# Microcontroller.net
KiCad netlist of a schematic drawn in Altium Designer
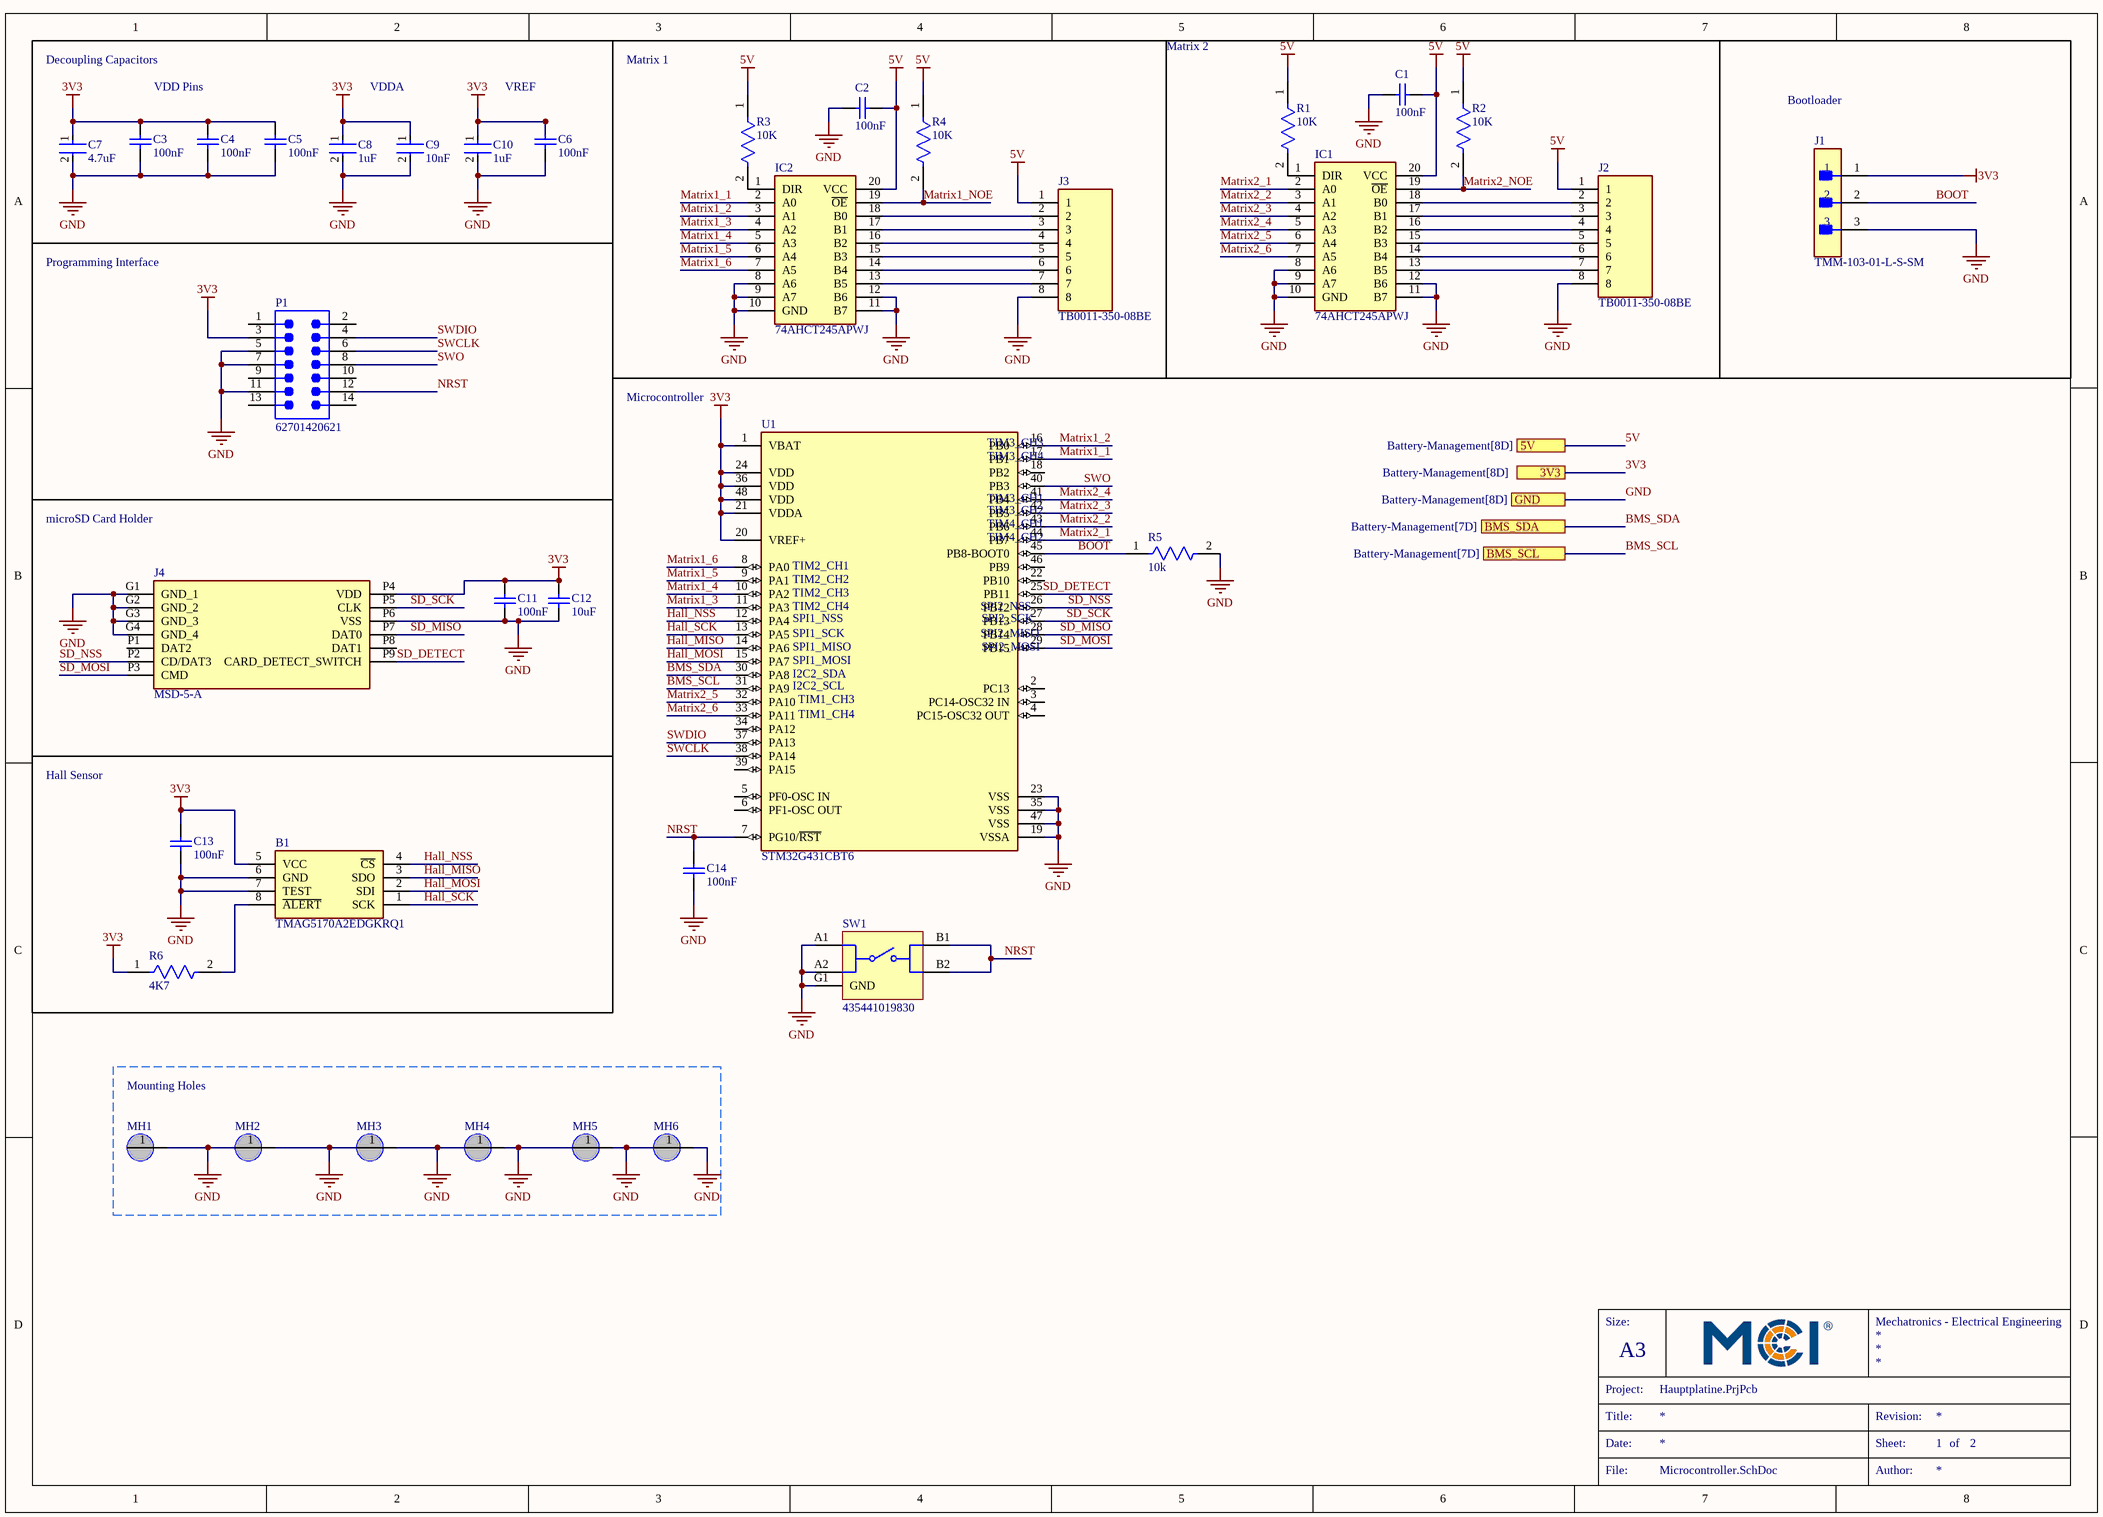
[diagram p0: Microcontroller.SchDoc]

(export (version "E")
  (design (tool "Eeschema 10.0.6"))
  (components
    (comp (ref "B1")
      (value "TMAG5170A2EDGKRQ1")
      (footprint "SOP65P490X110-8N")
      (description "Board Mount Hall Effect/Magnetic Sensors")
      (fields (field (name "MOUSER PART NUMBER") "595-MAG5170A2EDGKRQ1"))
      (libsource (lib "Library") (part "TMAG5170A2EDGKRQ1"))
    )
    (comp (ref "C1")
      (value "100nF")
      (footprint "CAPC2013X145X50LL20T20")
      (fields (field (name "PART NUMBER") "VJ0805Y104JXXPW1BC") (field (name "MANUFACTURER") "Vitramon"))
      (libsource (lib "Altium Content Vault") (part "CAP"))
    )
    (comp (ref "C2")
      (value "100nF")
      (footprint "CAPC2013X145X50LL20T20")
      (fields (field (name "PART NUMBER") "VJ0805Y104JXXPW1BC") (field (name "MANUFACTURER") "Vitramon"))
      (libsource (lib "Altium Content Vault") (part "CAP"))
    )
    (comp (ref "C3")
      (value "100nF")
      (footprint "CAPC2013X145X50LL20T20")
      (fields (field (name "PART NUMBER") "VJ0805Y104JXXPW1BC") (field (name "MANUFACTURER") "Vitramon"))
      (libsource (lib "Altium Content Vault") (part "CAP"))
    )
    (comp (ref "C4")
      (value "100nF")
      (footprint "CAPC2013X145X50LL20T20")
      (fields (field (name "PART NUMBER") "VJ0805Y104JXXPW1BC") (field (name "MANUFACTURER") "Vitramon"))
      (libsource (lib "Altium Content Vault") (part "CAP"))
    )
    (comp (ref "C5")
      (value "100nF")
      (footprint "CAPC2013X145X50LL20T20")
      (fields (field (name "PART NUMBER") "VJ0805Y104JXXPW1BC") (field (name "MANUFACTURER") "Vitramon"))
      (libsource (lib "Altium Content Vault") (part "CAP"))
    )
    (comp (ref "C6")
      (value "100nF")
      (footprint "CAPC2013X145X50LL20T20")
      (fields (field (name "PART NUMBER") "VJ0805Y104JXXPW1BC") (field (name "MANUFACTURER") "Vitramon"))
      (libsource (lib "Altium Content Vault") (part "CAP"))
    )
    (comp (ref "C7")
      (value "4.7uF")
      (footprint "FP-C0805C475K3RACAUTO-MFG")
      (description "CAP CER 0805 4.7UF 25V X7R  10%")
      (libsource (lib "Altium Content Vault") (part "b4654b650e69147ec39a6b967a45e02"))
    )
    (comp (ref "C8")
      (value "1uF")
      (footprint "FP-CC0805-EB-MFG")
      (description "CAP CER 1UF 6.3V X7R 0805")
      (fields (field (name "TOLERANCE") "10%"))
      (libsource (lib "Altium Content Vault") (part "b4654b650e69147ec39a6b967a45e02"))
    )
    (comp (ref "C9")
      (value "10nF")
      (footprint "FP-AC0805-0_85-MFG")
      (description "AC Series 0805 10 nF 100 V ±10% X7R Multilayer Ceramic Capacitor")
      (fields
        (field (name "MANUFACTURER") "Yageo")
        (field (name "OCTOPART") "https://octopart.com/ac0805krx7r0bb103-yageo-75656636")
      )
      (libsource (lib "Altium Content Vault") (part "11868f565c42a9108669ba33697ecf6"))
    )
    (comp (ref "C10")
      (value "1uF")
      (footprint "FP-CC0805-EB-MFG")
      (description "CAP CER 1UF 6.3V X7R 0805")
      (fields (field (name "TOLERANCE") "10%"))
      (libsource (lib "Altium Content Vault") (part "b4654b650e69147ec39a6b967a45e02"))
    )
    (comp (ref "C11")
      (value "100nF")
      (footprint "CAPC2013X145X50LL20T20")
      (fields (field (name "PART NUMBER") "VJ0805Y104JXXPW1BC") (field (name "MANUFACTURER") "Vitramon"))
      (libsource (lib "Altium Content Vault") (part "CAP"))
    )
    (comp (ref "C12")
      (value "10uF")
      (footprint "CAPC2013X140X50ML20T25")
      (fields
        (field (name "MANUFACTURER") "AVX Interconnect / Elco")
        (field (name "PART NUMBER") "0805ZC106KAT2A")
      )
      (libsource (lib "Altium Content Vault") (part "CAP"))
    )
    (comp (ref "C13")
      (value "100nF")
      (footprint "CAPC2013X145X50LL20T20")
      (fields (field (name "PART NUMBER") "VJ0805Y104JXXPW1BC") (field (name "MANUFACTURER") "Vitramon"))
      (libsource (lib "Altium Content Vault") (part "CAP"))
    )
    (comp (ref "C14")
      (value "100nF")
      (footprint "CAPC2013X145X50LL20T20")
      (fields (field (name "PART NUMBER") "VJ0805Y104JXXPW1BC") (field (name "MANUFACTURER") "Vitramon"))
      (libsource (lib "Altium Content Vault") (part "CAP"))
    )
    (comp (ref "IC1")
      (value "74AHCT245APWJ")
      (footprint "Library:SOP65P640X110-20N")
      (description "Integrated Circuit")
      (fields (field (name "MOUSER PART NUMBER") "771-74AHCT245APWJ"))
      (libsource (lib "*") (part "74AHCT245APWJ"))
    )
    (comp (ref "IC2")
      (value "74AHCT245APWJ")
      (footprint "Library:SOP65P640X110-20N")
      (description "Integrated Circuit")
      (fields (field (name "MOUSER PART NUMBER") "771-74AHCT245APWJ"))
      (libsource (lib "*") (part "74AHCT245APWJ"))
    )
    (comp (ref "J1")
      (value "TMM-103-01-L-S-SM")
      (footprint "FP-TMM-103-01-L-S-SM-MFG")
      (description "CONN HEADER SMD 3POS 2MM")
      (libsource (lib "Altium Content Vault") (part "0d3f023dd272f625e17a2be33dea85f"))
    )
    (comp (ref "J2")
      (value "TB0011-350-08BE")
      (footprint "TB0011-350-08BE")
      (description "Connector")
      (libsource (lib "Library") (part "TB0011-350-08BE"))
    )
    (comp (ref "J3")
      (value "TB0011-350-08BE")
      (footprint "TB0011-350-08BE")
      (description "Connector")
      (libsource (lib "Library") (part "TB0011-350-08BE"))
    )
    (comp (ref "J4")
      (value "MSD-5-A")
      (footprint "Library:MSD5A")
      (description "Connector")
      (fields (field (name "MOUSER PART NUMBER") "179-MSD-5-A"))
      (libsource (lib "Library") (part "MSD-5-A"))
    )
    (comp (ref "MH1")
      (value "MountingHole")
      (footprint "MTH")
      (libsource (lib "Motorsteuerung_V5") (part "MountingHole"))
    )
    (comp (ref "MH2")
      (value "MountingHole")
      (footprint "MTH")
      (libsource (lib "Motorsteuerung_V5") (part "MountingHole"))
    )
    (comp (ref "MH3")
      (value "MountingHole")
      (footprint "MTH")
      (libsource (lib "Motorsteuerung_V5") (part "MountingHole"))
    )
    (comp (ref "MH4")
      (value "MountingHole")
      (footprint "MTH")
      (libsource (lib "Motorsteuerung_V5") (part "MountingHole"))
    )
    (comp (ref "MH5")
      (value "MountingHole")
      (footprint "MTH")
      (libsource (lib "Motorsteuerung_V5") (part "MountingHole"))
    )
    (comp (ref "MH6")
      (value "MountingHole")
      (footprint "MTH")
      (libsource (lib "Motorsteuerung_V5") (part "MountingHole"))
    )
    (comp (ref "P1")
      (value "62701420621")
      (footprint "62701420621")
      (description "Conn, Hdr, 14Pos, 2Row, 1.27Mm, Smt Rohs Compliant: Yes")
      (libsource (lib "Altium Content Vault") (part "Header_Male_2R_14P"))
    )
    (comp (ref "R1")
      (value "10K")
      (footprint "FP-AT0805-MFG")
      (description "Thin Film Chip Resistors Automotive Grade 10kΩ 0.5% 50ppm/°C 0805")
      (fields (field (name "TOLERANCE") "0.5%"))
      (libsource (lib "Altium Content Vault") (part "1029c3af85768c4190bb7ad29bc67b5"))
    )
    (comp (ref "R2")
      (value "10K")
      (footprint "FP-AT0805-MFG")
      (description "Thin Film Chip Resistors Automotive Grade 10kΩ 0.5% 50ppm/°C 0805")
      (fields (field (name "TOLERANCE") "0.5%"))
      (libsource (lib "Altium Content Vault") (part "1029c3af85768c4190bb7ad29bc67b5"))
    )
    (comp (ref "R3")
      (value "10K")
      (footprint "FP-AT0805-MFG")
      (description "Thin Film Chip Resistors Automotive Grade 10kΩ 0.5% 50ppm/°C 0805")
      (fields (field (name "TOLERANCE") "0.5%"))
      (libsource (lib "Altium Content Vault") (part "1029c3af85768c4190bb7ad29bc67b5"))
    )
    (comp (ref "R4")
      (value "10K")
      (footprint "FP-AT0805-MFG")
      (description "Thin Film Chip Resistors Automotive Grade 10kΩ 0.5% 50ppm/°C 0805")
      (fields (field (name "TOLERANCE") "0.5%"))
      (libsource (lib "Altium Content Vault") (part "1029c3af85768c4190bb7ad29bc67b5"))
    )
    (comp (ref "R5")
      (value "10k")
      (footprint "FP-AT0805-MFG")
      (description "Thin Film Chip Resistors Automotive Grade 10kΩ 0.5% 50ppm/°C 0805")
      (fields (field (name "TOLERANCE") "0.5%"))
      (libsource (lib "Altium Content Vault") (part "1029c3af85768c4190bb7ad29bc67b5"))
    )
    (comp (ref "R6")
      (value "4K7")
      (footprint "FP-RT0805-MFG")
      (description "RES SMD 47K OHM 1% 1/8W 0805")
      (fields
        (field (name "MANUFACTURER PART NUMBER") "RT0805FRD0747KL")
        (field (name "OCTOPART") "https://octopart.com/rt0805frd0747kl-yageo-71400071")
      )
      (libsource (lib "Altium Content Vault") (part "1029c3af85768c4190bb7ad29bc67b5"))
    )
    (comp (ref "SW1")
      (value "435441019830")
      (footprint "435441019830")
      (description "Tactile Switch, 0.05A, 32Vdc, Smd, 300Gf Rohs Compliant: Yes")
      (libsource (lib "Altium Content Vault") (part "SPST-NO_4P_1GND"))
    )
    (comp (ref "U1")
      (value "STM32G431CBT6")
      (footprint "FP-LQFP48-5B-MFG")
      (description "MAINSTREAM ARM CORTEX-M4+ MCU 17")
      (fields
        (field (name "MANUFACTURER") "STMicroelectronics")
        (field (name "OCTOPART") "https://octopart.com/stm32g431cbt6-stmicroelectronics-98835224")
      )
      (libsource (lib "Altium Content Vault") (part "08b09c1d51ec08ade740842f2b8671b"))
    )
  )
  (nets
    (net (code "1") (name "/BMS_SCL") (class "Default")
      (node (ref "U1") (pin "31") (pinfunction "PA9_31") (pintype "bidirectional"))
    )
    (net (code "2") (name "/BMS_SDA") (class "Default")
      (node (ref "U1") (pin "30") (pinfunction "PA8_30") (pintype "bidirectional"))
    )
    (net (code "3") (name "/BOOT") (class "Default")
      (node (ref "J1") (pin "2") (pinfunction "2_2") (pintype "passive"))
      (node (ref "R5") (pin "1") (pinfunction "1_1") (pintype "passive"))
      (node (ref "U1") (pin "45") (pinfunction "PB8-BOOT0_45") (pintype "bidirectional"))
    )
    (net (code "4") (name "/Hall_MISO") (class "Default")
      (node (ref "B1") (pin "3") (pinfunction "SDO_3") (pintype "passive"))
      (node (ref "U1") (pin "14") (pinfunction "PA6_14") (pintype "bidirectional"))
    )
    (net (code "5") (name "/Hall_MOSI") (class "Default")
      (node (ref "B1") (pin "2") (pinfunction "SDI_2") (pintype "passive"))
      (node (ref "U1") (pin "15") (pinfunction "PA7_15") (pintype "bidirectional"))
    )
    (net (code "6") (name "/Hall_NSS") (class "Default")
      (node (ref "B1") (pin "4") (pinfunction "~{CS}_4") (pintype "passive"))
      (node (ref "U1") (pin "12") (pinfunction "PA4_12") (pintype "bidirectional"))
    )
    (net (code "7") (name "/Hall_SCK") (class "Default")
      (node (ref "B1") (pin "1") (pinfunction "SCK_1") (pintype "passive"))
      (node (ref "U1") (pin "13") (pinfunction "PA5_13") (pintype "bidirectional"))
    )
    (net (code "8") (name "/Matrix1_1") (class "Default")
      (node (ref "IC2") (pin "2") (pinfunction "A0_2") (pintype "passive"))
      (node (ref "U1") (pin "17") (pinfunction "PB1_17") (pintype "bidirectional"))
    )
    (net (code "9") (name "/Matrix1_2") (class "Default")
      (node (ref "IC2") (pin "3") (pinfunction "A1_3") (pintype "passive"))
      (node (ref "U1") (pin "16") (pinfunction "PB0_16") (pintype "bidirectional"))
    )
    (net (code "10") (name "/Matrix1_3") (class "Default")
      (node (ref "IC2") (pin "4") (pinfunction "A2_4") (pintype "passive"))
      (node (ref "U1") (pin "11") (pinfunction "PA3_11") (pintype "bidirectional"))
    )
    (net (code "11") (name "/Matrix1_4") (class "Default")
      (node (ref "IC2") (pin "5") (pinfunction "A3_5") (pintype "passive"))
      (node (ref "U1") (pin "10") (pinfunction "PA2_10") (pintype "bidirectional"))
    )
    (net (code "12") (name "/Matrix1_5") (class "Default")
      (node (ref "IC2") (pin "6") (pinfunction "A4_6") (pintype "passive"))
      (node (ref "U1") (pin "9") (pinfunction "PA1_9") (pintype "bidirectional"))
    )
    (net (code "13") (name "/Matrix1_6") (class "Default")
      (node (ref "IC2") (pin "7") (pinfunction "A5_7") (pintype "passive"))
      (node (ref "U1") (pin "8") (pinfunction "PA0_8") (pintype "bidirectional"))
    )
    (net (code "14") (name "/Matrix1_NOE") (class "Default")
      (node (ref "IC2") (pin "19") (pinfunction "~{OE}_19") (pintype "passive"))
      (node (ref "R4") (pin "2") (pinfunction "2_2") (pintype "passive"))
    )
    (net (code "15") (name "/Matrix2_1") (class "Default")
      (node (ref "IC1") (pin "2") (pinfunction "A0_2") (pintype "passive"))
      (node (ref "U1") (pin "44") (pinfunction "PB7_44") (pintype "bidirectional"))
    )
    (net (code "16") (name "/Matrix2_2") (class "Default")
      (node (ref "IC1") (pin "3") (pinfunction "A1_3") (pintype "passive"))
      (node (ref "U1") (pin "43") (pinfunction "PB6_43") (pintype "bidirectional"))
    )
    (net (code "17") (name "/Matrix2_3") (class "Default")
      (node (ref "IC1") (pin "4") (pinfunction "A2_4") (pintype "passive"))
      (node (ref "U1") (pin "42") (pinfunction "PB5_42") (pintype "bidirectional"))
    )
    (net (code "18") (name "/Matrix2_4") (class "Default")
      (node (ref "IC1") (pin "5") (pinfunction "A3_5") (pintype "passive"))
      (node (ref "U1") (pin "41") (pinfunction "PB4_41") (pintype "bidirectional"))
    )
    (net (code "19") (name "/Matrix2_5") (class "Default")
      (node (ref "IC1") (pin "6") (pinfunction "A4_6") (pintype "passive"))
      (node (ref "U1") (pin "32") (pinfunction "PA10_32") (pintype "bidirectional"))
    )
    (net (code "20") (name "/Matrix2_6") (class "Default")
      (node (ref "IC1") (pin "7") (pinfunction "A5_7") (pintype "passive"))
      (node (ref "U1") (pin "33") (pinfunction "PA11_33") (pintype "bidirectional"))
    )
    (net (code "21") (name "/Matrix2_NOE") (class "Default")
      (node (ref "IC1") (pin "19") (pinfunction "~{OE}_19") (pintype "passive"))
      (node (ref "R2") (pin "2") (pinfunction "2_2") (pintype "passive"))
    )
    (net (code "22") (name "/NRST") (class "Default")
      (node (ref "C14") (pin "2") (pinfunction "2_2") (pintype "passive"))
      (node (ref "P1") (pin "12") (pinfunction "12_12") (pintype "passive"))
      (node (ref "SW1") (pin "B1") (pinfunction "B1_B1") (pintype "passive"))
      (node (ref "SW1") (pin "B2") (pinfunction "B2_B2") (pintype "passive"))
      (node (ref "U1") (pin "7") (pinfunction "PG10/~{RST}_7") (pintype "bidirectional"))
    )
    (net (code "23") (name "/SD_DETECT") (class "Default")
      (node (ref "J4") (pin "P9") (pinfunction "CARD_DETECT_SWITCH_P9") (pintype "passive"))
      (node (ref "U1") (pin "25") (pinfunction "PB11_25") (pintype "bidirectional"))
    )
    (net (code "24") (name "/SD_MISO") (class "Default")
      (node (ref "J4") (pin "P7") (pinfunction "DAT0_P7") (pintype "passive"))
      (node (ref "U1") (pin "28") (pinfunction "PB14_28") (pintype "bidirectional"))
    )
    (net (code "25") (name "/SD_MOSI") (class "Default")
      (node (ref "J4") (pin "P3") (pinfunction "CMD_P3") (pintype "passive"))
      (node (ref "U1") (pin "29") (pinfunction "PB15_29") (pintype "bidirectional"))
    )
    (net (code "26") (name "/SD_NSS") (class "Default")
      (node (ref "J4") (pin "P2") (pinfunction "CD/DAT3_P2") (pintype "passive"))
      (node (ref "U1") (pin "26") (pinfunction "PB12_26") (pintype "bidirectional"))
    )
    (net (code "27") (name "/SD_SCK") (class "Default")
      (node (ref "J4") (pin "P5") (pinfunction "CLK_P5") (pintype "passive"))
      (node (ref "U1") (pin "27") (pinfunction "PB13_27") (pintype "bidirectional"))
    )
    (net (code "28") (name "/SWCLK") (class "Default")
      (node (ref "P1") (pin "6") (pinfunction "6_6") (pintype "passive"))
      (node (ref "U1") (pin "38") (pinfunction "PA14_38") (pintype "bidirectional"))
    )
    (net (code "29") (name "/SWDIO") (class "Default")
      (node (ref "P1") (pin "4") (pinfunction "4_4") (pintype "passive"))
      (node (ref "U1") (pin "37") (pinfunction "PA13_37") (pintype "bidirectional"))
    )
    (net (code "30") (name "/SWO") (class "Default")
      (node (ref "P1") (pin "8") (pinfunction "8_8") (pintype "passive"))
      (node (ref "U1") (pin "40") (pinfunction "PB3_40") (pintype "bidirectional"))
    )
    (net (code "31") (name "3V3") (class "Default")
      (node (ref "B1") (pin "5") (pinfunction "VCC_5") (pintype "passive"))
      (node (ref "C10") (pin "1") (pinfunction "1_1") (pintype "passive"))
      (node (ref "C11") (pin "1") (pinfunction "1_1") (pintype "passive"))
      (node (ref "C12") (pin "2") (pinfunction "2_2") (pintype "passive"))
      (node (ref "C13") (pin "2") (pinfunction "2_2") (pintype "passive"))
      (node (ref "C3") (pin "2") (pinfunction "2_2") (pintype "passive"))
      (node (ref "C4") (pin "2") (pinfunction "2_2") (pintype "passive"))
      (node (ref "C5") (pin "2") (pinfunction "2_2") (pintype "passive"))
      (node (ref "C6") (pin "2") (pinfunction "2_2") (pintype "passive"))
      (node (ref "C7") (pin "1") (pinfunction "1_1") (pintype "passive"))
      (node (ref "C8") (pin "1") (pinfunction "1_1") (pintype "passive"))
      (node (ref "C9") (pin "1") (pinfunction "1_1") (pintype "passive"))
      (node (ref "J1") (pin "1") (pinfunction "1_1") (pintype "passive"))
      (node (ref "J4") (pin "P4") (pinfunction "VDD_P4") (pintype "passive"))
      (node (ref "P1") (pin "3") (pinfunction "3_3") (pintype "passive"))
      (node (ref "R6") (pin "1") (pinfunction "1_1") (pintype "passive"))
      (node (ref "U1") (pin "1") (pinfunction "VBAT_1") (pintype "power_in"))
      (node (ref "U1") (pin "20") (pinfunction "VREF+_20") (pintype "power_in"))
      (node (ref "U1") (pin "21") (pinfunction "VDDA_21") (pintype "power_in"))
      (node (ref "U1") (pin "24") (pinfunction "VDD_24") (pintype "power_in"))
      (node (ref "U1") (pin "36") (pinfunction "VDD_36") (pintype "power_in"))
      (node (ref "U1") (pin "48") (pinfunction "VDD_48") (pintype "power_in"))
    )
    (net (code "32") (name "5V") (class "Default")
      (node (ref "C1") (pin "2") (pinfunction "2_2") (pintype "passive"))
      (node (ref "C2") (pin "2") (pinfunction "2_2") (pintype "passive"))
      (node (ref "IC1") (pin "20") (pinfunction "VCC_20") (pintype "passive"))
      (node (ref "IC2") (pin "20") (pinfunction "VCC_20") (pintype "passive"))
      (node (ref "J2") (pin "1") (pinfunction "1_1") (pintype "passive"))
      (node (ref "J3") (pin "1") (pinfunction "1_1") (pintype "passive"))
      (node (ref "R1") (pin "1") (pinfunction "1_1") (pintype "passive"))
      (node (ref "R2") (pin "1") (pinfunction "1_1") (pintype "passive"))
      (node (ref "R3") (pin "1") (pinfunction "1_1") (pintype "passive"))
      (node (ref "R4") (pin "1") (pinfunction "1_1") (pintype "passive"))
    )
    (net (code "33") (name "GND") (class "Default")
      (node (ref "B1") (pin "6") (pinfunction "GND_6") (pintype "passive"))
      (node (ref "B1") (pin "7") (pinfunction "TEST_7") (pintype "passive"))
      (node (ref "C1") (pin "1") (pinfunction "1_1") (pintype "passive"))
      (node (ref "C10") (pin "2") (pinfunction "2_2") (pintype "passive"))
      (node (ref "C11") (pin "2") (pinfunction "2_2") (pintype "passive"))
      (node (ref "C12") (pin "1") (pinfunction "1_1") (pintype "passive"))
      (node (ref "C13") (pin "1") (pinfunction "1_1") (pintype "passive"))
      (node (ref "C14") (pin "1") (pinfunction "1_1") (pintype "passive"))
      (node (ref "C2") (pin "1") (pinfunction "1_1") (pintype "passive"))
      (node (ref "C3") (pin "1") (pinfunction "1_1") (pintype "passive"))
      (node (ref "C4") (pin "1") (pinfunction "1_1") (pintype "passive"))
      (node (ref "C5") (pin "1") (pinfunction "1_1") (pintype "passive"))
      (node (ref "C6") (pin "1") (pinfunction "1_1") (pintype "passive"))
      (node (ref "C7") (pin "2") (pinfunction "2_2") (pintype "passive"))
      (node (ref "C8") (pin "2") (pinfunction "2_2") (pintype "passive"))
      (node (ref "C9") (pin "2") (pinfunction "2_2") (pintype "passive"))
      (node (ref "IC1") (pin "10") (pinfunction "GND_10") (pintype "passive"))
      (node (ref "IC1") (pin "11") (pinfunction "B7_11") (pintype "passive"))
      (node (ref "IC1") (pin "12") (pinfunction "B6_12") (pintype "passive"))
      (node (ref "IC1") (pin "8") (pinfunction "A6_8") (pintype "passive"))
      (node (ref "IC1") (pin "9") (pinfunction "A7_9") (pintype "passive"))
      (node (ref "IC2") (pin "10") (pinfunction "GND_10") (pintype "passive"))
      (node (ref "IC2") (pin "11") (pinfunction "B7_11") (pintype "passive"))
      (node (ref "IC2") (pin "12") (pinfunction "B6_12") (pintype "passive"))
      (node (ref "IC2") (pin "8") (pinfunction "A6_8") (pintype "passive"))
      (node (ref "IC2") (pin "9") (pinfunction "A7_9") (pintype "passive"))
      (node (ref "J1") (pin "3") (pinfunction "3_3") (pintype "passive"))
      (node (ref "J2") (pin "8") (pinfunction "8_8") (pintype "passive"))
      (node (ref "J3") (pin "8") (pinfunction "8_8") (pintype "passive"))
      (node (ref "J4") (pin "G1") (pinfunction "GND_1_G1") (pintype "passive"))
      (node (ref "J4") (pin "G2") (pinfunction "GND_2_G2") (pintype "passive"))
      (node (ref "J4") (pin "G3") (pinfunction "GND_3_G3") (pintype "passive"))
      (node (ref "J4") (pin "G4") (pinfunction "GND_4_G4") (pintype "passive"))
      (node (ref "J4") (pin "P6") (pinfunction "VSS_P6") (pintype "passive"))
      (node (ref "MH1") (pin "1") (pintype "passive"))
      (node (ref "MH2") (pin "1") (pintype "passive"))
      (node (ref "MH3") (pin "1") (pintype "passive"))
      (node (ref "MH4") (pin "1") (pintype "passive"))
      (node (ref "MH5") (pin "1") (pintype "passive"))
      (node (ref "MH6") (pin "1") (pintype "passive"))
      (node (ref "P1") (pin "11") (pinfunction "11_11") (pintype "passive"))
      (node (ref "P1") (pin "5") (pinfunction "5_5") (pintype "passive"))
      (node (ref "P1") (pin "7") (pinfunction "7_7") (pintype "passive"))
      (node (ref "R5") (pin "2") (pinfunction "2_2") (pintype "passive"))
      (node (ref "SW1") (pin "A1") (pinfunction "A1_A1") (pintype "passive"))
      (node (ref "SW1") (pin "A2") (pinfunction "A2_A2") (pintype "passive"))
      (node (ref "SW1") (pin "G1") (pinfunction "GND_G1") (pintype "passive"))
      (node (ref "U1") (pin "19") (pinfunction "VSSA_19") (pintype "power_in"))
      (node (ref "U1") (pin "23") (pinfunction "VSS_23") (pintype "power_in"))
      (node (ref "U1") (pin "35") (pinfunction "VSS_35") (pintype "power_in"))
      (node (ref "U1") (pin "47") (pinfunction "VSS_47") (pintype "power_in"))
    )
    (net (code "34") (name "Net-(B1-~{ALERT})") (class "Default")
      (node (ref "B1") (pin "8") (pinfunction "~{ALERT}_8") (pintype "passive"))
      (node (ref "R6") (pin "2") (pinfunction "2_2") (pintype "passive"))
    )
    (net (code "35") (name "Net-(IC1-B0)") (class "Default")
      (node (ref "IC1") (pin "18") (pinfunction "B0_18") (pintype "passive"))
      (node (ref "J2") (pin "2") (pinfunction "2_2") (pintype "passive"))
    )
    (net (code "36") (name "Net-(IC1-B1)") (class "Default")
      (node (ref "IC1") (pin "17") (pinfunction "B1_17") (pintype "passive"))
      (node (ref "J2") (pin "3") (pinfunction "3_3") (pintype "passive"))
    )
    (net (code "37") (name "Net-(IC1-B2)") (class "Default")
      (node (ref "IC1") (pin "16") (pinfunction "B2_16") (pintype "passive"))
      (node (ref "J2") (pin "4") (pinfunction "4_4") (pintype "passive"))
    )
    (net (code "38") (name "Net-(IC1-B3)") (class "Default")
      (node (ref "IC1") (pin "15") (pinfunction "B3_15") (pintype "passive"))
      (node (ref "J2") (pin "5") (pinfunction "5_5") (pintype "passive"))
    )
    (net (code "39") (name "Net-(IC1-B4)") (class "Default")
      (node (ref "IC1") (pin "14") (pinfunction "B4_14") (pintype "passive"))
      (node (ref "J2") (pin "6") (pinfunction "6_6") (pintype "passive"))
    )
    (net (code "40") (name "Net-(IC1-B5)") (class "Default")
      (node (ref "IC1") (pin "13") (pinfunction "B5_13") (pintype "passive"))
      (node (ref "J2") (pin "7") (pinfunction "7_7") (pintype "passive"))
    )
    (net (code "41") (name "Net-(IC1-DIR)") (class "Default")
      (node (ref "IC1") (pin "1") (pinfunction "DIR_1") (pintype "passive"))
      (node (ref "R1") (pin "2") (pinfunction "2_2") (pintype "passive"))
    )
    (net (code "42") (name "Net-(IC2-B0)") (class "Default")
      (node (ref "IC2") (pin "18") (pinfunction "B0_18") (pintype "passive"))
      (node (ref "J3") (pin "2") (pinfunction "2_2") (pintype "passive"))
    )
    (net (code "43") (name "Net-(IC2-B1)") (class "Default")
      (node (ref "IC2") (pin "17") (pinfunction "B1_17") (pintype "passive"))
      (node (ref "J3") (pin "3") (pinfunction "3_3") (pintype "passive"))
    )
    (net (code "44") (name "Net-(IC2-B2)") (class "Default")
      (node (ref "IC2") (pin "16") (pinfunction "B2_16") (pintype "passive"))
      (node (ref "J3") (pin "4") (pinfunction "4_4") (pintype "passive"))
    )
    (net (code "45") (name "Net-(IC2-B3)") (class "Default")
      (node (ref "IC2") (pin "15") (pinfunction "B3_15") (pintype "passive"))
      (node (ref "J3") (pin "5") (pinfunction "5_5") (pintype "passive"))
    )
    (net (code "46") (name "Net-(IC2-B4)") (class "Default")
      (node (ref "IC2") (pin "14") (pinfunction "B4_14") (pintype "passive"))
      (node (ref "J3") (pin "6") (pinfunction "6_6") (pintype "passive"))
    )
    (net (code "47") (name "Net-(IC2-B5)") (class "Default")
      (node (ref "IC2") (pin "13") (pinfunction "B5_13") (pintype "passive"))
      (node (ref "J3") (pin "7") (pinfunction "7_7") (pintype "passive"))
    )
    (net (code "48") (name "Net-(IC2-DIR)") (class "Default")
      (node (ref "IC2") (pin "1") (pinfunction "DIR_1") (pintype "passive"))
      (node (ref "R3") (pin "2") (pinfunction "2_2") (pintype "passive"))
    )
    (net (code "49") (name "unconnected-(J4-DAT1-PadP8)") (class "Default")
      (node (ref "J4") (pin "P8") (pinfunction "DAT1_P8") (pintype "passive"))
    )
    (net (code "50") (name "unconnected-(J4-DAT2-PadP1)") (class "Default")
      (node (ref "J4") (pin "P1") (pinfunction "DAT2_P1") (pintype "passive"))
    )
    (net (code "51") (name "unconnected-(P1-Pad1)") (class "Default")
      (node (ref "P1") (pin "1") (pinfunction "1_1") (pintype "passive"))
    )
    (net (code "52") (name "unconnected-(P1-Pad2)") (class "Default")
      (node (ref "P1") (pin "2") (pinfunction "2_2") (pintype "passive"))
    )
    (net (code "53") (name "unconnected-(P1-Pad9)") (class "Default")
      (node (ref "P1") (pin "9") (pinfunction "9_9") (pintype "passive"))
    )
    (net (code "54") (name "unconnected-(P1-Pad10)") (class "Default")
      (node (ref "P1") (pin "10") (pinfunction "10_10") (pintype "passive"))
    )
    (net (code "55") (name "unconnected-(P1-Pad13)") (class "Default")
      (node (ref "P1") (pin "13") (pinfunction "13_13") (pintype "passive"))
    )
    (net (code "56") (name "unconnected-(P1-Pad14)") (class "Default")
      (node (ref "P1") (pin "14") (pinfunction "14_14") (pintype "passive"))
    )
    (net (code "57") (name "unconnected-(U1-PA12-Pad34)") (class "Default")
      (node (ref "U1") (pin "34") (pinfunction "PA12_34") (pintype "bidirectional"))
    )
    (net (code "58") (name "unconnected-(U1-PA15-Pad39)") (class "Default")
      (node (ref "U1") (pin "39") (pinfunction "PA15_39") (pintype "bidirectional"))
    )
    (net (code "59") (name "unconnected-(U1-PB2-Pad18)") (class "Default")
      (node (ref "U1") (pin "18") (pinfunction "PB2_18") (pintype "bidirectional"))
    )
    (net (code "60") (name "unconnected-(U1-PB9-Pad46)") (class "Default")
      (node (ref "U1") (pin "46") (pinfunction "PB9_46") (pintype "bidirectional"))
    )
    (net (code "61") (name "unconnected-(U1-PB10-Pad22)") (class "Default")
      (node (ref "U1") (pin "22") (pinfunction "PB10_22") (pintype "bidirectional"))
    )
    (net (code "62") (name "unconnected-(U1-PC13-Pad2)") (class "Default")
      (node (ref "U1") (pin "2") (pinfunction "PC13_2") (pintype "bidirectional"))
    )
    (net (code "63") (name "unconnected-(U1-PC14-OSC32_IN-Pad3)") (class "Default")
      (node (ref "U1") (pin "3") (pinfunction "PC14-OSC32_IN_3") (pintype "bidirectional"))
    )
    (net (code "64") (name "unconnected-(U1-PC15-OSC32_OUT-Pad4)") (class "Default")
      (node (ref "U1") (pin "4") (pinfunction "PC15-OSC32_OUT_4") (pintype "bidirectional"))
    )
    (net (code "65") (name "unconnected-(U1-PF0-OSC_IN-Pad5)") (class "Default")
      (node (ref "U1") (pin "5") (pinfunction "PF0-OSC_IN_5") (pintype "bidirectional"))
    )
    (net (code "66") (name "unconnected-(U1-PF1-OSC_OUT-Pad6)") (class "Default")
      (node (ref "U1") (pin "6") (pinfunction "PF1-OSC_OUT_6") (pintype "bidirectional"))
    )
  )
)
